# Miranda_McMickens_Final_Light.net
KiCad netlist of a schematic drawn in EAGLE
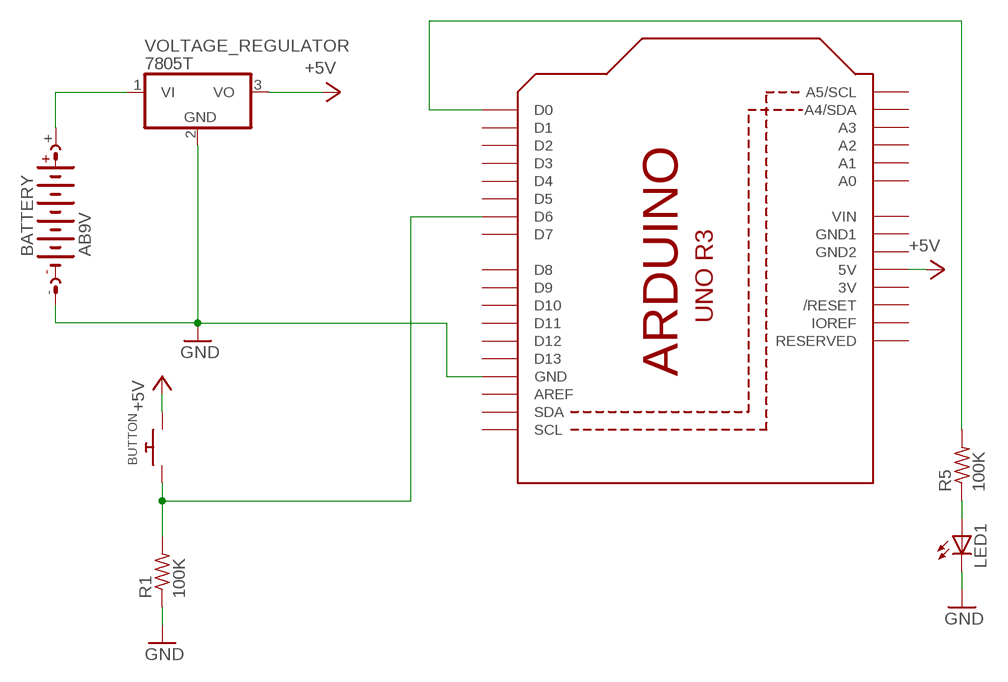
[diagram p0: schematic, sheet 1]

(export (version "E")
  (design (tool "Eeschema 10.0.6"))
  (components
    (comp (ref "BATTERY")
      (value "AB9V")
      (footprint "eagle-import:AB9V")
      (libsource (lib "eagle-import") (part "AB9V"))
    )
    (comp (ref "BUTTON")
      (value "SWITCH_PUSHBUTTONSOFTTOUCHSMD_SJ")
      (footprint "eagle-import:PUSHBUTTON_SMD_SJ")
      (libsource (lib "eagle-import") (part "SWITCH_PUSHBUTTONSOFTTOUCHSMD_SJ"))
    )
    (comp (ref "LED1")
      (value "LED5MM")
      (footprint "eagle-import:LED5MM")
      (libsource (lib "eagle-import") (part "LED5MM"))
    )
    (comp (ref "R1")
      (value "100K")
      (footprint "eagle-import:M0805")
      (libsource (lib "eagle-import") (part "R-US_M0805"))
    )
    (comp (ref "R5")
      (value "100K")
      (footprint "eagle-import:M0805")
      (libsource (lib "eagle-import") (part "R-US_M0805"))
    )
    (comp (ref "U1")
      (value "ARDUINOR3-BPLACE")
      (footprint "eagle-import:ARDUINOR3-BPLACE")
      (libsource (lib "eagle-import") (part "ARDUINOR3-BPLACE"))
    )
    (comp (ref "VOLTAGE_REGULATOR")
      (value "7805T")
      (footprint "eagle-import:TO220H")
      (libsource (lib "eagle-import") (part "78T05"))
    )
  )
  (nets
    (net (code "1") (name "+5V") (class "Default")
      (node (ref "BUTTON") (pin "P$2") (pinfunction "P$2_P$2") (pintype "passive"))
      (node (ref "U1") (pin "5V") (pinfunction "5V_5V") (pintype "power_in"))
      (node (ref "VOLTAGE_REGULATOR") (pin "3") (pinfunction "VO_3") (pintype "passive"))
    )
    (net (code "2") (name "/3V") (class "Default")
      (node (ref "U1") (pin "3V") (pinfunction "3V_3V") (pintype "power_in"))
    )
    (net (code "3") (name "/GND1") (class "Default")
      (node (ref "U1") (pin "GND1") (pinfunction "GND1_GND1") (pintype "power_in"))
    )
    (net (code "4") (name "/GND2") (class "Default")
      (node (ref "U1") (pin "GND2") (pinfunction "GND2_GND2") (pintype "power_in"))
    )
    (net (code "5") (name "/VIN") (class "Default")
      (node (ref "U1") (pin "VIN") (pinfunction "VIN_VIN") (pintype "power_in"))
    )
    (net (code "6") (name "GND") (class "Default")
      (node (ref "BATTERY") (pin "-") (pinfunction "-_-") (pintype "passive"))
      (node (ref "LED1") (pin "K") (pinfunction "C_K") (pintype "passive"))
      (node (ref "R1") (pin "1") (pinfunction "1_1") (pintype "passive"))
      (node (ref "U1") (pin "GND") (pinfunction "GND_GND") (pintype "power_in"))
      (node (ref "VOLTAGE_REGULATOR") (pin "2") (pinfunction "GND_2") (pintype "passive"))
    )
    (net (code "7") (name "Net-(BUTTON-PadP$1)") (class "Default")
      (node (ref "BUTTON") (pin "P$1") (pinfunction "P$1_P$1") (pintype "passive"))
      (node (ref "R1") (pin "2") (pinfunction "2_2") (pintype "passive"))
      (node (ref "U1") (pin "D6") (pinfunction "D6_D6") (pintype "bidirectional"))
    )
    (net (code "8") (name "Net-(LED1-PadA)") (class "Default")
      (node (ref "LED1") (pin "A") (pinfunction "A_A") (pintype "passive"))
      (node (ref "R5") (pin "1") (pinfunction "1_1") (pintype "passive"))
    )
    (net (code "9") (name "Net-(R5-Pad2)") (class "Default")
      (node (ref "R5") (pin "2") (pinfunction "2_2") (pintype "passive"))
      (node (ref "U1") (pin "D0") (pinfunction "D0_D0") (pintype "bidirectional"))
    )
    (net (code "10") (name "Net-(VOLTAGE_REGULATOR-VI)") (class "Default")
      (node (ref "BATTERY") (pin "+") (pinfunction "+_+") (pintype "passive"))
      (node (ref "VOLTAGE_REGULATOR") (pin "1") (pinfunction "VI_1") (pintype "input"))
    )
    (net (code "11") (name "unconnected-(U1-A4{slash}SDA-PadA4)") (class "Default")
      (node (ref "U1") (pin "A4") (pinfunction "A4/SDA_A4") (pintype "bidirectional"))
    )
    (net (code "12") (name "unconnected-(U1-A5{slash}SCL-PadA5)") (class "Default")
      (node (ref "U1") (pin "A5") (pinfunction "A5/SCL_A5") (pintype "bidirectional"))
    )
    (net (code "13") (name "unconnected-(U1-PadA0)") (class "Default")
      (node (ref "U1") (pin "A0") (pinfunction "A0_A0") (pintype "bidirectional"))
    )
    (net (code "14") (name "unconnected-(U1-PadA1)") (class "Default")
      (node (ref "U1") (pin "A1") (pinfunction "A1_A1") (pintype "bidirectional"))
    )
    (net (code "15") (name "unconnected-(U1-PadA2)") (class "Default")
      (node (ref "U1") (pin "A2") (pinfunction "A2_A2") (pintype "bidirectional"))
    )
    (net (code "16") (name "unconnected-(U1-PadA3)") (class "Default")
      (node (ref "U1") (pin "A3") (pinfunction "A3_A3") (pintype "bidirectional"))
    )
    (net (code "17") (name "unconnected-(U1-PadAREF)") (class "Default")
      (node (ref "U1") (pin "AREF") (pinfunction "AREF_AREF") (pintype "bidirectional"))
    )
    (net (code "18") (name "unconnected-(U1-PadD1)") (class "Default")
      (node (ref "U1") (pin "D1") (pinfunction "D1_D1") (pintype "bidirectional"))
    )
    (net (code "19") (name "unconnected-(U1-PadD2)") (class "Default")
      (node (ref "U1") (pin "D2") (pinfunction "D2_D2") (pintype "bidirectional"))
    )
    (net (code "20") (name "unconnected-(U1-PadD3)") (class "Default")
      (node (ref "U1") (pin "D3") (pinfunction "D3_D3") (pintype "bidirectional"))
    )
    (net (code "21") (name "unconnected-(U1-PadD4)") (class "Default")
      (node (ref "U1") (pin "D4") (pinfunction "D4_D4") (pintype "bidirectional"))
    )
    (net (code "22") (name "unconnected-(U1-PadD5)") (class "Default")
      (node (ref "U1") (pin "D5") (pinfunction "D5_D5") (pintype "bidirectional"))
    )
    (net (code "23") (name "unconnected-(U1-PadD7)") (class "Default")
      (node (ref "U1") (pin "D7") (pinfunction "D7_D7") (pintype "bidirectional"))
    )
    (net (code "24") (name "unconnected-(U1-PadD8)") (class "Default")
      (node (ref "U1") (pin "D8") (pinfunction "D8_D8") (pintype "bidirectional"))
    )
    (net (code "25") (name "unconnected-(U1-PadD9)") (class "Default")
      (node (ref "U1") (pin "D9") (pinfunction "D9_D9") (pintype "bidirectional"))
    )
    (net (code "26") (name "unconnected-(U1-PadD10)") (class "Default")
      (node (ref "U1") (pin "D10") (pinfunction "D10_D10") (pintype "bidirectional"))
    )
    (net (code "27") (name "unconnected-(U1-PadD11)") (class "Default")
      (node (ref "U1") (pin "D11") (pinfunction "D11_D11") (pintype "bidirectional"))
    )
    (net (code "28") (name "unconnected-(U1-PadD12)") (class "Default")
      (node (ref "U1") (pin "D12") (pinfunction "D12_D12") (pintype "bidirectional"))
    )
    (net (code "29") (name "unconnected-(U1-PadD13)") (class "Default")
      (node (ref "U1") (pin "D13") (pinfunction "D13_D13") (pintype "bidirectional"))
    )
    (net (code "30") (name "unconnected-(U1-PadIOREF)") (class "Default")
      (node (ref "U1") (pin "IOREF") (pinfunction "IOREF_IOREF") (pintype "output"))
    )
    (net (code "31") (name "unconnected-(U1-PadRESERVED)") (class "Default")
      (node (ref "U1") (pin "RESERVED") (pinfunction "RESERVED_RESERVED") (pintype "no_connect"))
    )
    (net (code "32") (name "unconnected-(U1-PadSCL)") (class "Default")
      (node (ref "U1") (pin "SCL") (pinfunction "SCL_SCL") (pintype "bidirectional"))
    )
    (net (code "33") (name "unconnected-(U1-PadSDA)") (class "Default")
      (node (ref "U1") (pin "SDA") (pinfunction "SDA_SDA") (pintype "bidirectional"))
    )
    (net (code "34") (name "unconnected-(U1-{slash}RESET-PadRESET)") (class "Default")
      (node (ref "U1") (pin "RESET") (pinfunction "/RESET_RESET") (pintype "bidirectional"))
    )
  )
)
